# Switching_Regulator.net
KiCad netlist of a schematic drawn in Altium Designer
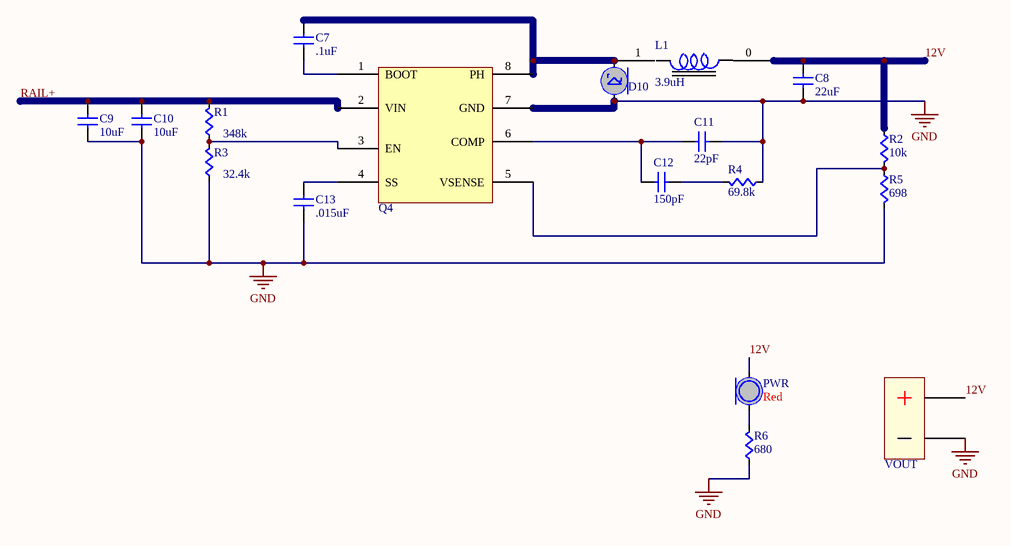
[diagram p0: Switching_Regulator.SchDoc]

(export (version "E")
  (design (tool "Eeschema 10.0.6"))
  (components
    (comp (ref "C7")
      (value ".1uF")
      (footprint "CAPC0603")
      (fields (field (name "Comment") "Cap"))
      (libsource (lib "Passives") (part "Cap"))
    )
    (comp (ref "C8")
      (value "22uF")
      (footprint "CAPC1206")
      (fields (field (name "Comment") "Cap"))
      (libsource (lib "Passives") (part "Cap"))
    )
    (comp (ref "C9")
      (value "10uF")
      (footprint "CAPC0603")
      (fields (field (name "Comment") "Cap"))
      (libsource (lib "Passives") (part "Cap"))
    )
    (comp (ref "C10")
      (value "10uF")
      (footprint "CAPC0603")
      (fields (field (name "Comment") "Cap"))
      (libsource (lib "Passives") (part "Cap"))
    )
    (comp (ref "C11")
      (value "22pF")
      (footprint "CAPC0603")
      (fields (field (name "Comment") "Cap"))
      (libsource (lib "Passives") (part "Cap"))
    )
    (comp (ref "C12")
      (value "150pF")
      (footprint "CAPC0603")
      (fields (field (name "Comment") "Cap"))
      (libsource (lib "Passives") (part "Cap"))
    )
    (comp (ref "C13")
      (value ".015uF")
      (footprint "CAPC0603")
      (fields (field (name "Comment") "Cap"))
      (libsource (lib "Passives") (part "Cap"))
    )
    (comp (ref "D10")
      (value "DFLS160")
      (footprint "RSX501L-20TE25")
      (description "1.0A Surface Mount Schottky Barrier Rectifier")
      (libsource (lib "Semiconductors") (part "DFLS160"))
    )
    (comp (ref "L1")
      (value "37392C")
      (footprint "37392C")
      (description "INDUCTOR 3.90UH 10.0A SMD")
      (fields (field (name "ALTIUM_UNNAMED_1") "3.9uH"))
      (libsource (lib "Passives") (part "37392C"))
    )
    (comp (ref "PWR")
      (value "LED")
      (footprint "LED0603")
      (fields (field (name "COLOR") "Red"))
      (libsource (lib "SubjuGator8") (part "LED"))
    )
    (comp (ref "Q4")
      (value "TPS54332DDA")
      (footprint "TPS54332DDA")
      (description "IC REG BUCK ADJ 3.5A 8SOPWRPAD")
      (libsource (lib "ICs") (part "TPS54332DDA"))
    )
    (comp (ref "R1")
      (value "348k")
      (footprint "RES0603")
      (fields (field (name "Comment") "Res"))
      (libsource (lib "Passives") (part "Res"))
    )
    (comp (ref "R2")
      (value "10k")
      (footprint "RES0603")
      (fields (field (name "Comment") "Res"))
      (libsource (lib "Passives") (part "Res"))
    )
    (comp (ref "R3")
      (value "32.4k")
      (footprint "RES0603")
      (fields (field (name "Comment") "Res"))
      (libsource (lib "Passives") (part "Res"))
    )
    (comp (ref "R4")
      (value "69.8k")
      (footprint "RES0603")
      (fields (field (name "Comment") "Res"))
      (libsource (lib "Passives") (part "Res"))
    )
    (comp (ref "R5")
      (value "698")
      (footprint "RES0603")
      (fields (field (name "Comment") "Res"))
      (libsource (lib "Passives") (part "Res"))
    )
    (comp (ref "R6")
      (value "680")
      (footprint "RES0603")
      (fields (field (name "Comment") "Res"))
      (libsource (lib "SubjuGator8") (part "Res"))
    )
    (comp (ref "VOUT")
      (value "BATWIRE")
      (footprint "BATWIRE12")
      (description "Two large gauge leads soldered directly to the board.")
      (libsource (lib "Connectors") (part "BATWIRE"))
    )
  )
  (nets
    (net (code "1") (name "/12V") (class "Default")
      (node (ref "C8") (pin "1") (pinfunction "A_1") (pintype "passive"))
      (node (ref "L1") (pin "0") (pinfunction "0_0") (pintype "passive"))
      (node (ref "PWR") (pin "A") (pinfunction "A_A") (pintype "passive"))
      (node (ref "R2") (pin "2") (pinfunction "B_2") (pintype "passive"))
      (node (ref "VOUT") (pin "+") (pinfunction "+_+") (pintype "power_in"))
    )
    (net (code "2") (name "/RAIL+") (class "Default")
      (node (ref "C10") (pin "1") (pinfunction "A_1") (pintype "passive"))
      (node (ref "C9") (pin "1") (pinfunction "A_1") (pintype "passive"))
      (node (ref "Q4") (pin "2") (pinfunction "VIN_2") (pintype "passive"))
      (node (ref "R1") (pin "1") (pinfunction "A_1") (pintype "passive"))
    )
    (net (code "3") (name "GND") (class "Default")
      (node (ref "C10") (pin "2") (pinfunction "B_2") (pintype "passive"))
      (node (ref "C11") (pin "2") (pinfunction "B_2") (pintype "passive"))
      (node (ref "C13") (pin "2") (pinfunction "B_2") (pintype "passive"))
      (node (ref "C8") (pin "2") (pinfunction "B_2") (pintype "passive"))
      (node (ref "C9") (pin "2") (pinfunction "B_2") (pintype "passive"))
      (node (ref "D10") (pin "A") (pinfunction "A_A") (pintype "passive"))
      (node (ref "Q4") (pin "7") (pinfunction "GND_7") (pintype "passive"))
      (node (ref "R3") (pin "2") (pinfunction "B_2") (pintype "passive"))
      (node (ref "R4") (pin "2") (pinfunction "B_2") (pintype "passive"))
      (node (ref "R5") (pin "1") (pinfunction "A_1") (pintype "passive"))
      (node (ref "R6") (pin "2") (pinfunction "B_2") (pintype "passive"))
      (node (ref "VOUT") (pin "-") (pinfunction "-_-") (pintype "power_in"))
    )
    (net (code "4") (name "Net-(C7-A)") (class "Default")
      (node (ref "C7") (pin "1") (pinfunction "A_1") (pintype "passive"))
      (node (ref "D10") (pin "C") (pinfunction "C_C") (pintype "passive"))
      (node (ref "L1") (pin "1") (pinfunction "1_1") (pintype "passive"))
      (node (ref "Q4") (pin "8") (pinfunction "PH_8") (pintype "passive"))
    )
    (net (code "5") (name "Net-(C7-B)") (class "Default")
      (node (ref "C7") (pin "2") (pinfunction "B_2") (pintype "passive"))
      (node (ref "Q4") (pin "1") (pinfunction "BOOT_1") (pintype "passive"))
    )
    (net (code "6") (name "Net-(C11-A)") (class "Default")
      (node (ref "C11") (pin "1") (pinfunction "A_1") (pintype "passive"))
      (node (ref "C12") (pin "1") (pinfunction "A_1") (pintype "passive"))
      (node (ref "Q4") (pin "6") (pinfunction "COMP_6") (pintype "passive"))
    )
    (net (code "7") (name "Net-(C12-B)") (class "Default")
      (node (ref "C12") (pin "2") (pinfunction "B_2") (pintype "passive"))
      (node (ref "R4") (pin "1") (pinfunction "A_1") (pintype "passive"))
    )
    (net (code "8") (name "Net-(C13-A)") (class "Default")
      (node (ref "C13") (pin "1") (pinfunction "A_1") (pintype "passive"))
      (node (ref "Q4") (pin "4") (pinfunction "SS_4") (pintype "passive"))
    )
    (net (code "9") (name "Net-(Q4-EN)") (class "Default")
      (node (ref "Q4") (pin "3") (pinfunction "EN_3") (pintype "passive"))
      (node (ref "R1") (pin "2") (pinfunction "B_2") (pintype "passive"))
      (node (ref "R3") (pin "1") (pinfunction "A_1") (pintype "passive"))
    )
    (net (code "10") (name "Net-(Q4-VSENSE)") (class "Default")
      (node (ref "Q4") (pin "5") (pinfunction "VSENSE_5") (pintype "passive"))
      (node (ref "R2") (pin "1") (pinfunction "A_1") (pintype "passive"))
      (node (ref "R5") (pin "2") (pinfunction "B_2") (pintype "passive"))
    )
    (net (code "11") (name "Net-(R6-A)") (class "Default")
      (node (ref "PWR") (pin "C") (pinfunction "C_C") (pintype "passive"))
      (node (ref "R6") (pin "1") (pinfunction "A_1") (pintype "passive"))
    )
  )
)
